# Soil_Moisture_Sensor.net
KiCad netlist of a schematic drawn in EAGLE
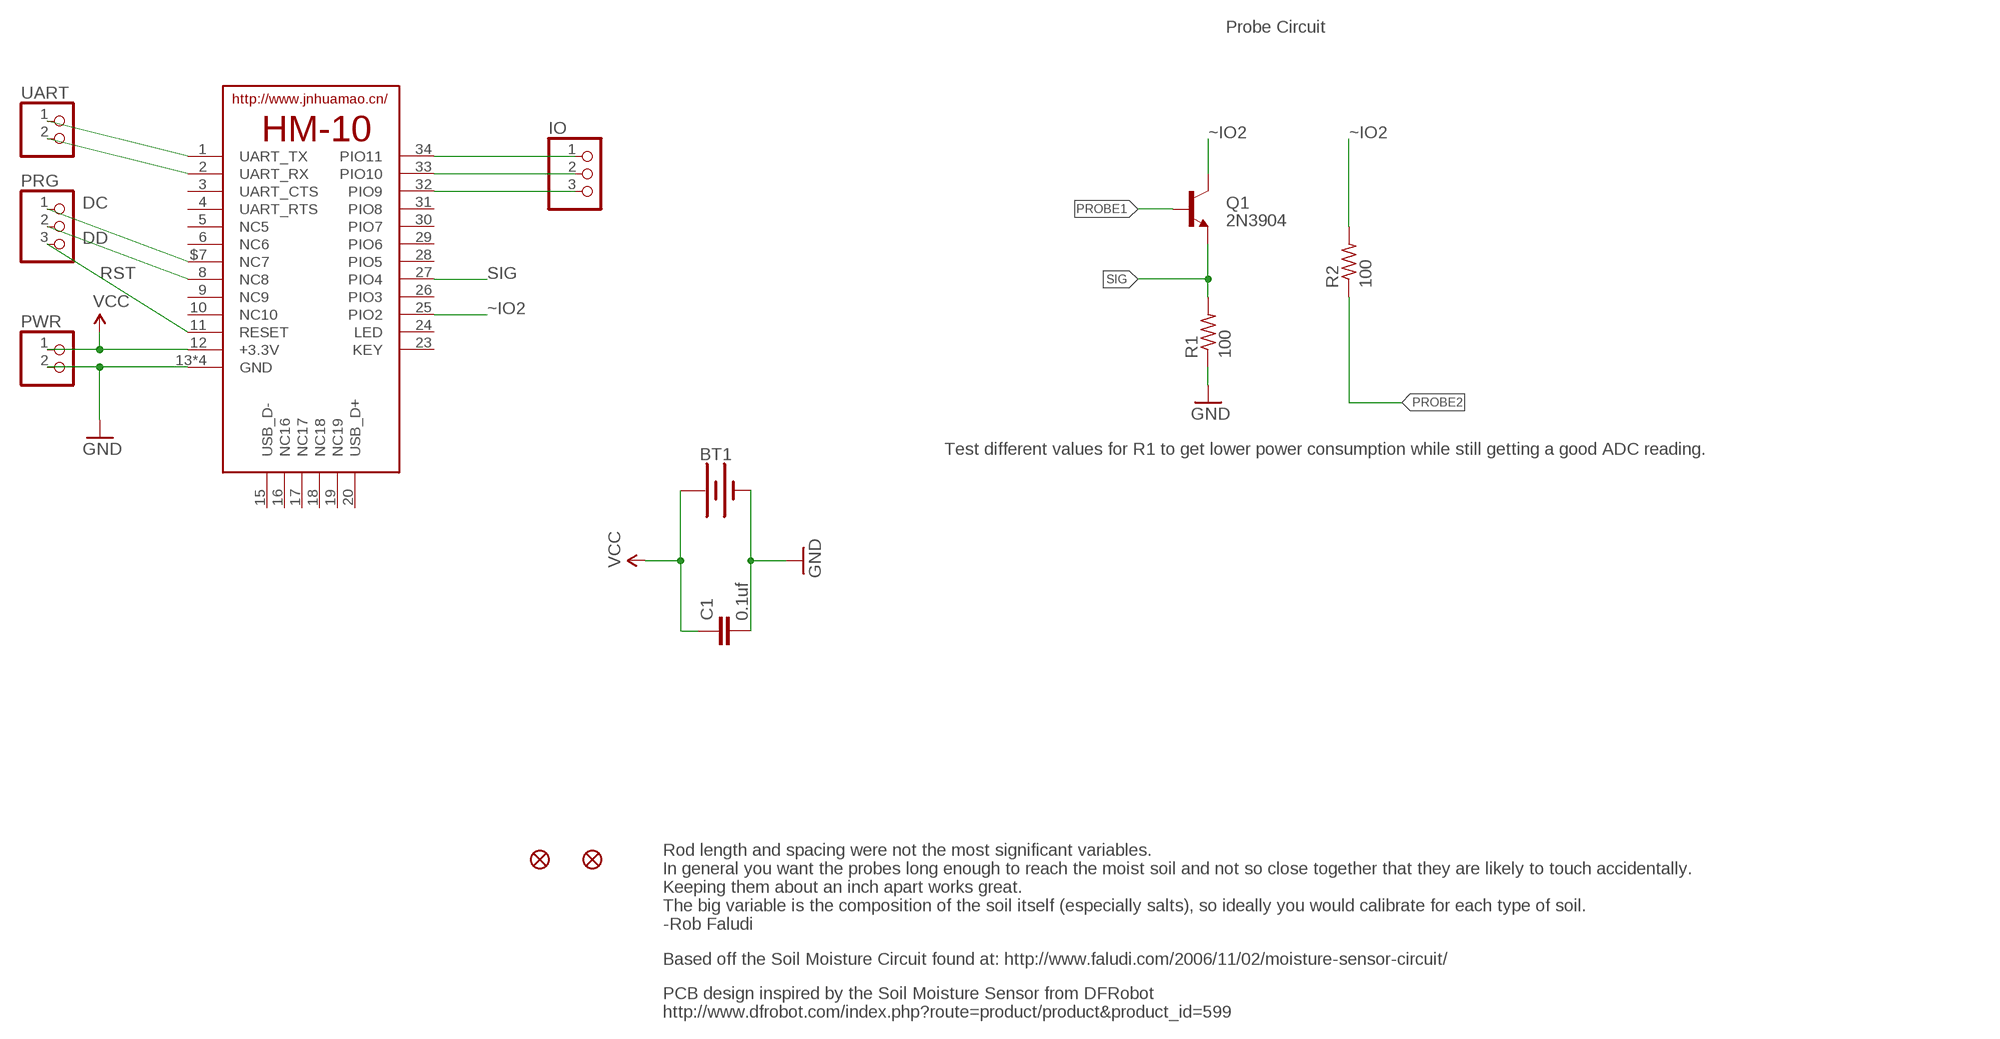
[diagram p0: schematic, sheet 1]

(export (version "E")
  (design (tool "Eeschema 10.0.6"))
  (components
    (comp (ref "BT1")
      (value "BATTERY-20MM_SMD_4LEGS")
      (footprint "eagle-import:BATTCON_20MM_4LEGS")
      (libsource (lib "eagle-import") (part "BATTERY-20MM_SMD_4LEGS"))
    )
    (comp (ref "C1")
      (value "0.1uf")
      (footprint "eagle-import:C0805")
      (libsource (lib "eagle-import") (part "C-EUC0805"))
    )
    (comp (ref "FD1")
      (value "FIDUCIAL1X2")
      (footprint "eagle-import:FIDUCIAL-1X2")
      (libsource (lib "eagle-import") (part "FIDUCIAL1X2"))
    )
    (comp (ref "FD2")
      (value "FIDUCIAL1X2")
      (footprint "eagle-import:FIDUCIAL-1X2")
      (libsource (lib "eagle-import") (part "FIDUCIAL1X2"))
    )
    (comp (ref "HM-10")
      (value "HM-10-BOARD")
      (footprint "eagle-import:26.9X13X2.2_BOARD")
      (libsource (lib "eagle-import") (part "HM-10-BOARD"))
    )
    (comp (ref "IO")
      (value "PINHD-1X3")
      (footprint "eagle-import:1X03")
      (libsource (lib "eagle-import") (part "PINHD-1X3"))
    )
    (comp (ref "PRG")
      (value "PINHD-1X3")
      (footprint "eagle-import:1X03")
      (libsource (lib "eagle-import") (part "PINHD-1X3"))
    )
    (comp (ref "PWR")
      (value "PINHD-1X2")
      (footprint "eagle-import:1X02")
      (libsource (lib "eagle-import") (part "PINHD-1X2"))
    )
    (comp (ref "Q1")
      (value "2N3904")
      (footprint "eagle-import:SOT23-3")
      (libsource (lib "eagle-import") (part "TRANSISTOR_NPNMMBT2222A"))
    )
    (comp (ref "R1")
      (value "100")
      (footprint "eagle-import:R0805")
      (libsource (lib "eagle-import") (part "R-US_R0805"))
    )
    (comp (ref "R2")
      (value "100")
      (footprint "eagle-import:R0805")
      (libsource (lib "eagle-import") (part "R-US_R0805"))
    )
    (comp (ref "UART")
      (value "PINHD-1X2")
      (footprint "eagle-import:1X02")
      (libsource (lib "eagle-import") (part "PINHD-1X2"))
    )
  )
  (nets
    (net (code "1") (name "/DC") (class "Default")
      (node (ref "HM-10") (pin "$7") (pinfunction "NC7_$7") (pintype "bidirectional"))
      (node (ref "PRG") (pin "1") (pinfunction "1_1") (pintype "passive"))
    )
    (net (code "2") (name "/DD") (class "Default")
      (node (ref "HM-10") (pin "8") (pinfunction "NC8_8") (pintype "bidirectional"))
      (node (ref "PRG") (pin "2") (pinfunction "2_2") (pintype "passive"))
    )
    (net (code "3") (name "/RST") (class "Default")
      (node (ref "HM-10") (pin "11") (pinfunction "RESET_11") (pintype "bidirectional"))
      (node (ref "PRG") (pin "3") (pinfunction "3_3") (pintype "passive"))
    )
    (net (code "4") (name "/~{IO2}") (class "Default")
      (node (ref "HM-10") (pin "25") (pinfunction "PIO2_25") (pintype "bidirectional"))
      (node (ref "Q1") (pin "3") (pinfunction "C_3") (pintype "passive"))
      (node (ref "R2") (pin "2") (pinfunction "2_2") (pintype "passive"))
    )
    (net (code "5") (name "GND") (class "Default")
      (node (ref "BT1") (pin "NEGATIVE") (pinfunction "-_NEGATIVE") (pintype "power_in"))
      (node (ref "C1") (pin "2") (pinfunction "2_2") (pintype "passive"))
      (node (ref "HM-10") (pin "13") (pinfunction "GND_13") (pintype "bidirectional"))
      (node (ref "HM-10") (pin "14") (pinfunction "GND_14") (pintype "bidirectional"))
      (node (ref "HM-10") (pin "21") (pinfunction "GND_21") (pintype "bidirectional"))
      (node (ref "HM-10") (pin "22") (pinfunction "GND_22") (pintype "bidirectional"))
      (node (ref "PWR") (pin "2") (pinfunction "2_2") (pintype "passive"))
      (node (ref "R1") (pin "1") (pinfunction "1_1") (pintype "passive"))
    )
    (net (code "6") (name "Net-(HM-10-PIO9)") (class "Default")
      (node (ref "HM-10") (pin "32") (pinfunction "PIO9_32") (pintype "bidirectional"))
      (node (ref "IO") (pin "3") (pinfunction "3_3") (pintype "passive"))
    )
    (net (code "7") (name "Net-(HM-10-PIO10)") (class "Default")
      (node (ref "HM-10") (pin "33") (pinfunction "PIO10_33") (pintype "bidirectional"))
      (node (ref "IO") (pin "2") (pinfunction "2_2") (pintype "passive"))
    )
    (net (code "8") (name "Net-(HM-10-PIO11)") (class "Default")
      (node (ref "HM-10") (pin "34") (pinfunction "PIO11_34") (pintype "bidirectional"))
      (node (ref "IO") (pin "1") (pinfunction "1_1") (pintype "passive"))
    )
    (net (code "9") (name "Net-(HM-10-UART_RX)") (class "Default")
      (node (ref "HM-10") (pin "2") (pinfunction "UART_RX_2") (pintype "bidirectional"))
      (node (ref "UART") (pin "2") (pinfunction "2_2") (pintype "passive"))
    )
    (net (code "10") (name "Net-(HM-10-UART_TX)") (class "Default")
      (node (ref "HM-10") (pin "1") (pinfunction "UART_TX_1") (pintype "bidirectional"))
      (node (ref "UART") (pin "1") (pinfunction "1_1") (pintype "passive"))
    )
    (net (code "11") (name "PROBE1") (class "Default")
      (node (ref "Q1") (pin "1") (pinfunction "B_1") (pintype "passive"))
    )
    (net (code "12") (name "PROBE2") (class "Default")
      (node (ref "R2") (pin "1") (pinfunction "1_1") (pintype "passive"))
    )
    (net (code "13") (name "SIG") (class "Default")
      (node (ref "HM-10") (pin "27") (pinfunction "PIO4_27") (pintype "bidirectional"))
      (node (ref "Q1") (pin "2") (pinfunction "E_2") (pintype "passive"))
      (node (ref "R1") (pin "2") (pinfunction "2_2") (pintype "passive"))
    )
    (net (code "14") (name "VCC") (class "Default")
      (node (ref "BT1") (pin "POSITIVE@1") (pinfunction "+_POSITIVE@1") (pintype "power_in"))
      (node (ref "BT1") (pin "POSITIVE@2") (pinfunction "+_POSITIVE@2") (pintype "power_in"))
      (node (ref "BT1") (pin "POSITIVE@3") (pinfunction "+_POSITIVE@3") (pintype "power_in"))
      (node (ref "BT1") (pin "POSITIVE@4") (pinfunction "+_POSITIVE@4") (pintype "power_in"))
      (node (ref "C1") (pin "1") (pinfunction "1_1") (pintype "passive"))
      (node (ref "HM-10") (pin "12") (pinfunction "+3.3V_12") (pintype "bidirectional"))
      (node (ref "PWR") (pin "1") (pinfunction "1_1") (pintype "passive"))
    )
    (net (code "15") (name "unconnected-(HM-10-KEY-Pad23)") (class "Default")
      (node (ref "HM-10") (pin "23") (pinfunction "KEY_23") (pintype "bidirectional"))
    )
    (net (code "16") (name "unconnected-(HM-10-LED-Pad24)") (class "Default")
      (node (ref "HM-10") (pin "24") (pinfunction "LED_24") (pintype "bidirectional"))
    )
    (net (code "17") (name "unconnected-(HM-10-NC5-Pad5)") (class "Default")
      (node (ref "HM-10") (pin "5") (pinfunction "NC5_5") (pintype "bidirectional"))
    )
    (net (code "18") (name "unconnected-(HM-10-NC6-Pad6)") (class "Default")
      (node (ref "HM-10") (pin "6") (pinfunction "NC6_6") (pintype "bidirectional"))
    )
    (net (code "19") (name "unconnected-(HM-10-NC9-Pad9)") (class "Default")
      (node (ref "HM-10") (pin "9") (pinfunction "NC9_9") (pintype "bidirectional"))
    )
    (net (code "20") (name "unconnected-(HM-10-NC10-Pad10)") (class "Default")
      (node (ref "HM-10") (pin "10") (pinfunction "NC10_10") (pintype "bidirectional"))
    )
    (net (code "21") (name "unconnected-(HM-10-NC16-Pad16)") (class "Default")
      (node (ref "HM-10") (pin "16") (pinfunction "NC16_16") (pintype "bidirectional"))
    )
    (net (code "22") (name "unconnected-(HM-10-NC17-Pad17)") (class "Default")
      (node (ref "HM-10") (pin "17") (pinfunction "NC17_17") (pintype "bidirectional"))
    )
    (net (code "23") (name "unconnected-(HM-10-NC18-Pad18)") (class "Default")
      (node (ref "HM-10") (pin "18") (pinfunction "NC18_18") (pintype "bidirectional"))
    )
    (net (code "24") (name "unconnected-(HM-10-NC19-Pad19)") (class "Default")
      (node (ref "HM-10") (pin "19") (pinfunction "NC19_19") (pintype "bidirectional"))
    )
    (net (code "25") (name "unconnected-(HM-10-PIO3-Pad26)") (class "Default")
      (node (ref "HM-10") (pin "26") (pinfunction "PIO3_26") (pintype "bidirectional"))
    )
    (net (code "26") (name "unconnected-(HM-10-PIO5-Pad28)") (class "Default")
      (node (ref "HM-10") (pin "28") (pinfunction "PIO5_28") (pintype "bidirectional"))
    )
    (net (code "27") (name "unconnected-(HM-10-PIO6-Pad29)") (class "Default")
      (node (ref "HM-10") (pin "29") (pinfunction "PIO6_29") (pintype "bidirectional"))
    )
    (net (code "28") (name "unconnected-(HM-10-PIO7-Pad30)") (class "Default")
      (node (ref "HM-10") (pin "30") (pinfunction "PIO7_30") (pintype "bidirectional"))
    )
    (net (code "29") (name "unconnected-(HM-10-PIO8-Pad31)") (class "Default")
      (node (ref "HM-10") (pin "31") (pinfunction "PIO8_31") (pintype "bidirectional"))
    )
    (net (code "30") (name "unconnected-(HM-10-UART_CTS-Pad3)") (class "Default")
      (node (ref "HM-10") (pin "3") (pinfunction "UART_CTS_3") (pintype "bidirectional"))
    )
    (net (code "31") (name "unconnected-(HM-10-UART_RTS-Pad4)") (class "Default")
      (node (ref "HM-10") (pin "4") (pinfunction "UART_RTS_4") (pintype "bidirectional"))
    )
    (net (code "32") (name "unconnected-(HM-10-USB_D+-Pad20)") (class "Default")
      (node (ref "HM-10") (pin "20") (pinfunction "USB_D+_20") (pintype "bidirectional"))
    )
    (net (code "33") (name "unconnected-(HM-10-USB_D--Pad15)") (class "Default")
      (node (ref "HM-10") (pin "15") (pinfunction "USB_D-_15") (pintype "bidirectional"))
    )
  )
)
